# STM32_V3.net
KiCad netlist of a schematic drawn in Altium Designer
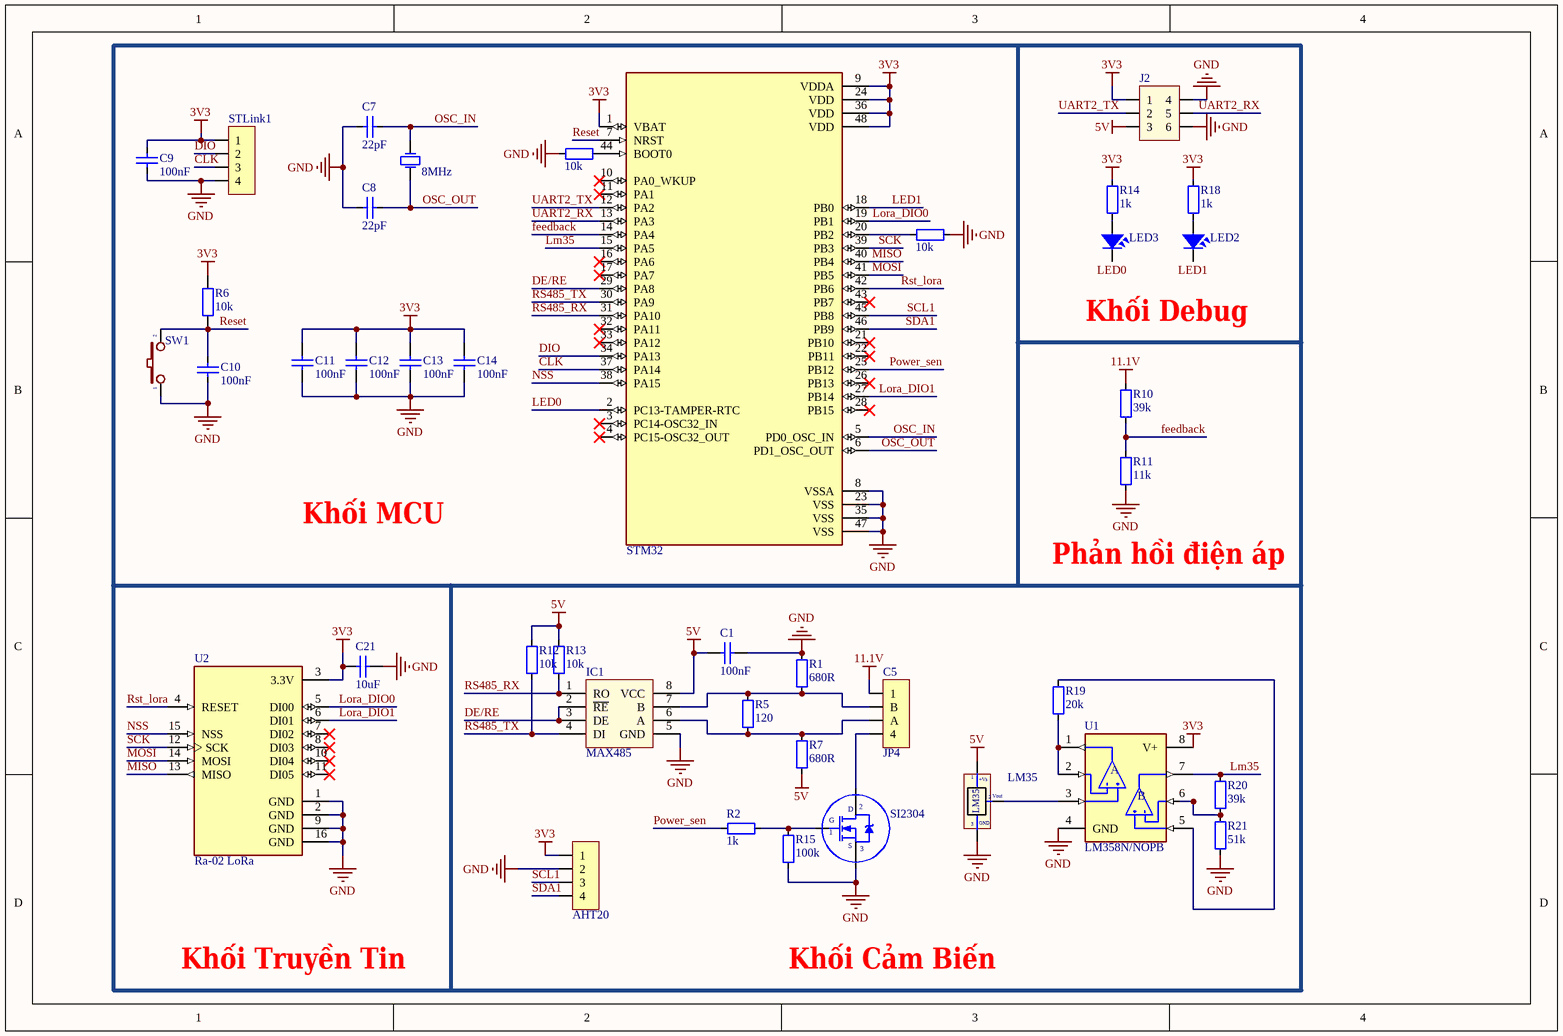
[diagram p0: STM32_V3.SchDoc]

(export (version "E")
  (design (tool "Eeschema 10.0.6"))
  (components
    (comp (ref "C1")
      (value "100nF")
      (footprint "CAP_0805")
      (description "Capacitor")
      (fields (field (name "PUBLISHER") "Altium Limited"))
      (libsource (lib "My Library") (part "CapSMD"))
    )
    (comp (ref "C5")
      (value "JP4")
      (footprint "KF4-5.08")
      (description "WR-PHD 2.54 mm Angled Socket Header")
      (fields
        (field (name "MANUFACTURER") "Würth Elektronik eiSos GmbH")
        (field (name "PARTNO") "613004143121")
        (field (name "CREATED BY") "Karrer Zheng")
      )
      (libsource (lib "") (part "JP4_1"))
    )
    (comp (ref "C7")
      (value "22pF")
      (footprint "CAP_0805")
      (description "Capacitor")
      (fields (field (name "PUBLISHER") "Altium Limited"))
      (libsource (lib "") (part "CapSMD_1"))
    )
    (comp (ref "C8")
      (value "22pF")
      (footprint "CAP_0805")
      (description "Capacitor")
      (fields (field (name "PUBLISHER") "Altium Limited"))
      (libsource (lib "") (part "CapSMD_1"))
    )
    (comp (ref "C9")
      (value "100nF")
      (footprint "CAP_0805")
      (description "Capacitor")
      (fields (field (name "PUBLISHER") "Altium Limited"))
      (libsource (lib "") (part "CapSMD_1"))
    )
    (comp (ref "C10")
      (value "100nF")
      (footprint "CAP_0805")
      (description "Capacitor")
      (fields (field (name "PUBLISHER") "Altium Limited"))
      (libsource (lib "") (part "CapSMD_1"))
    )
    (comp (ref "C11")
      (value "100nF")
      (footprint "CAP_0805")
      (description "Capacitor")
      (fields (field (name "PUBLISHER") "Altium Limited"))
      (libsource (lib "My Library") (part "CapSMD"))
    )
    (comp (ref "C12")
      (value "100nF")
      (footprint "CAP_0805")
      (description "Capacitor")
      (fields (field (name "PUBLISHER") "Altium Limited"))
      (libsource (lib "My Library") (part "CapSMD"))
    )
    (comp (ref "C13")
      (value "100nF")
      (footprint "CAP_0805")
      (description "Capacitor")
      (fields (field (name "PUBLISHER") "Altium Limited"))
      (libsource (lib "My Library") (part "CapSMD"))
    )
    (comp (ref "C14")
      (value "100nF")
      (footprint "CAP_0805")
      (description "Capacitor")
      (fields (field (name "PUBLISHER") "Altium Limited"))
      (libsource (lib "My Library") (part "CapSMD"))
    )
    (comp (ref "C19")
      (value "AHT20")
      (footprint "JP4-C1T")
      (description "WR-PHD 2.54 mm Angled Socket Header")
      (fields
        (field (name "MANUFACTURER") "Würth Elektronik eiSos GmbH")
        (field (name "PARTNO") "613004143121")
        (field (name "CREATED BY") "Karrer Zheng")
      )
      (libsource (lib "My Library") (part "JP4"))
    )
    (comp (ref "C21")
      (value "10uF")
      (footprint "CAP_0805")
      (description "Capacitor")
      (fields (field (name "PUBLISHER") "Altium Limited"))
      (libsource (lib "My Library") (part "CapSMD"))
    )
    (comp (ref "IC1")
      (value "MAX485")
      (footprint "SO-8")
      (description "RS232 - RS485 (Same sn75176)")
      (libsource (lib "My Library") (part "MAX485"))
    )
    (comp (ref "J2") (value "Connector 3x2") (footprint "JP3x2") (libsource (lib "hphonglib") (part "JP3x2")))
    (comp (ref "LED2")
      (value "LED")
      (footprint "LED-0805-Blue")
      (description "LED Single colour Green and Red")
      (libsource (lib "My Library") (part "LED"))
    )
    (comp (ref "LED3")
      (value "LED")
      (footprint "LED-0805-Blue")
      (description "LED Single colour Green and Red")
      (libsource (lib "My Library") (part "LED"))
    )
    (comp (ref "M1")
      (value "SI2304")
      (footprint "SOT23A")
      (description "Generic N Channel MOSFET")
      (libsource (lib "My Library") (part "MOSFET_N"))
    )
    (comp (ref "R1")
      (value "680R")
      (footprint "RES-SMD-0805")
      (description "Resistor")
      (fields
        (field (name "MANUFACTURER") "Generic Components")
        (field (name "PUBLISHER") "Altium Hobart Technology Centre")
      )
      (libsource (lib "My Library") (part "Resistor - SMD"))
    )
    (comp (ref "R2")
      (value "1k")
      (footprint "RES-SMD-0805")
      (description "Resistor")
      (fields
        (field (name "MANUFACTURER") "Generic Components")
        (field (name "PUBLISHER") "Altium Hobart Technology Centre")
      )
      (libsource (lib "My Library") (part "Resistor - SMD"))
    )
    (comp (ref "R3")
      (value "10k")
      (footprint "RES-SMD-0805")
      (description "Resistor")
      (fields
        (field (name "MANUFACTURER") "Generic Components")
        (field (name "PUBLISHER") "Altium Hobart Technology Centre")
      )
      (libsource (lib "My Library") (part "Resistor - SMD"))
    )
    (comp (ref "R5")
      (value "120")
      (footprint "RES-SMD-0805")
      (description "Resistor")
      (fields
        (field (name "MANUFACTURER") "Generic Components")
        (field (name "PUBLISHER") "Altium Hobart Technology Centre")
      )
      (libsource (lib "My Library") (part "Resistor - SMD"))
    )
    (comp (ref "R6")
      (value "10k")
      (footprint "RES_SMD_0805")
      (description "Resistor SMD")
      (fields
        (field (name "MANUFACTURER") "Generic Components")
        (field (name "PUBLISHER") "Altium Hobart Technology Centre")
      )
      (libsource (lib "") (part "Resistor - SMD_1"))
    )
    (comp (ref "R7")
      (value "680R")
      (footprint "RES-SMD-0805")
      (description "Resistor")
      (fields
        (field (name "MANUFACTURER") "Generic Components")
        (field (name "PUBLISHER") "Altium Hobart Technology Centre")
      )
      (libsource (lib "My Library") (part "Resistor - SMD"))
    )
    (comp (ref "R10")
      (value "39k")
      (footprint "RES-SMD-0805")
      (description "Resistor")
      (fields
        (field (name "MANUFACTURER") "Generic Components")
        (field (name "PUBLISHER") "Altium Hobart Technology Centre")
      )
      (libsource (lib "My Library") (part "Resistor - SMD"))
    )
    (comp (ref "R11")
      (value "11k")
      (footprint "RES-SMD-0805")
      (description "Resistor")
      (fields
        (field (name "MANUFACTURER") "Generic Components")
        (field (name "PUBLISHER") "Altium Hobart Technology Centre")
      )
      (libsource (lib "My Library") (part "Resistor - SMD"))
    )
    (comp (ref "R12")
      (value "10k")
      (footprint "RES-SMD-0805")
      (description "Resistor")
      (fields
        (field (name "MANUFACTURER") "Generic Components")
        (field (name "PUBLISHER") "Altium Hobart Technology Centre")
      )
      (libsource (lib "My Library") (part "Resistor - SMD"))
    )
    (comp (ref "R13")
      (value "10k")
      (footprint "RES-SMD-0805")
      (description "Resistor")
      (fields
        (field (name "MANUFACTURER") "Generic Components")
        (field (name "PUBLISHER") "Altium Hobart Technology Centre")
      )
      (libsource (lib "My Library") (part "Resistor - SMD"))
    )
    (comp (ref "R14")
      (value "1k")
      (footprint "RES-SMD-0805")
      (description "Resistor")
      (fields
        (field (name "MANUFACTURER") "Generic Components")
        (field (name "PUBLISHER") "Altium Hobart Technology Centre")
      )
      (libsource (lib "My Library") (part "Resistor - SMD"))
    )
    (comp (ref "R15")
      (value "100k")
      (footprint "RES-SMD-0805")
      (description "Resistor")
      (fields
        (field (name "MANUFACTURER") "Generic Components")
        (field (name "PUBLISHER") "Altium Hobart Technology Centre")
      )
      (libsource (lib "My Library") (part "Resistor - SMD"))
    )
    (comp (ref "R17")
      (value "10k")
      (footprint "RES-SMD-0805")
      (description "Resistor")
      (fields
        (field (name "MANUFACTURER") "Generic Components")
        (field (name "PUBLISHER") "Altium Hobart Technology Centre")
      )
      (libsource (lib "My Library") (part "Resistor - SMD"))
    )
    (comp (ref "R18")
      (value "1k")
      (footprint "RES-SMD-0805")
      (description "Resistor")
      (fields
        (field (name "MANUFACTURER") "Generic Components")
        (field (name "PUBLISHER") "Altium Hobart Technology Centre")
      )
      (libsource (lib "My Library") (part "Resistor - SMD"))
    )
    (comp (ref "R19")
      (value "20k")
      (footprint "RES-SMD-0805")
      (description "Resistor")
      (fields
        (field (name "MANUFACTURER") "Generic Components")
        (field (name "PUBLISHER") "Altium Hobart Technology Centre")
      )
      (libsource (lib "My Library") (part "Resistor - SMD"))
    )
    (comp (ref "R20")
      (value "39k")
      (footprint "RES-SMD-0805")
      (description "Resistor")
      (fields
        (field (name "MANUFACTURER") "Generic Components")
        (field (name "PUBLISHER") "Altium Hobart Technology Centre")
      )
      (libsource (lib "My Library") (part "Resistor - SMD"))
    )
    (comp (ref "R21")
      (value "51k")
      (footprint "RES-SMD-0805")
      (description "Resistor")
      (fields
        (field (name "MANUFACTURER") "Generic Components")
        (field (name "PUBLISHER") "Altium Hobart Technology Centre")
      )
      (libsource (lib "My Library") (part "Resistor - SMD"))
    )
    (comp (ref "STLink1")
      (value "JP4")
      (footprint "JP4-C1T")
      (description "WR-PHD 2.54 mm Angled Socket Header")
      (fields
        (field (name "MANUFACTURER") "Würth Elektronik eiSos GmbH")
        (field (name "PARTNO") "613004143121")
        (field (name "CREATED BY") "Karrer Zheng")
      )
      (libsource (lib "My Library") (part "JP4"))
    )
    (comp (ref "STM32")
      (value "STM32")
      (footprint "LQFP 48")
      (description "STM32 ARM-based 32-bit MCU with 64 Kbytes Flash, 64-pin LQFP, Industrial Temperature")
      (libsource (lib "My Library") (part "STM32F103C8T6"))
    )
    (comp (ref "SW1")
      (value "SW")
      (footprint "SW-SMD")
      (description "Switch button 2 pin")
      (libsource (lib "My Library") (part "SW2"))
    )
    (comp (ref "U1")
      (value "LM358N/NOPB")
      (footprint "SOIC8")
      (description "General Purpose Amplifier 2 Circuit - 8-PDIP")
      (fields (field (name "MF") "ON Semiconductor") (field (name "MP") "LM358N"))
      (libsource (lib "LM358N_NOPB") (part "LM358N/NOPB"))
    )
    (comp (ref "U2")
      (value "Ra-02 LoRa")
      (footprint "Ra-02")
      (description "LoRa Module Ra-02")
      (libsource (lib "My Library") (part "Ra-02 LoRa"))
    )
    (comp (ref "U3")
      (value "LM35")
      (footprint "QTO-92")
      (description "Teminal")
      (libsource (lib "My Library") (part "LM35"))
    )
    (comp (ref "Y1")
      (value "8MHz")
      (footprint "XTAL")
      (description "Crystal Oscillator")
      (fields (field (name "PUBLISHER") "Altium Limited"))
      (libsource (lib "My Library") (part "XTAL"))
    )
  )
  (nets
    (net (code "1") (name "/CLK") (class "Default")
      (node (ref "STLink1") (pin "3") (pinfunction "3_3") (pintype "passive"))
      (node (ref "STM32") (pin "37") (pinfunction "PA14_37") (pintype "bidirectional"))
    )
    (net (code "2") (name "/DE{slash}RE") (class "Default")
      (node (ref "IC1") (pin "2") (pinfunction "~{RE}_2") (pintype "passive"))
      (node (ref "IC1") (pin "3") (pinfunction "DE_3") (pintype "passive"))
      (node (ref "STM32") (pin "29") (pinfunction "PA8_29") (pintype "bidirectional"))
    )
    (net (code "3") (name "/DIO") (class "Default")
      (node (ref "STLink1") (pin "2") (pinfunction "2_2") (pintype "passive"))
      (node (ref "STM32") (pin "34") (pinfunction "PA13_34") (pintype "bidirectional"))
    )
    (net (code "4") (name "/LED0") (class "Default")
      (node (ref "LED3") (pin "2") (pinfunction "2_2") (pintype "passive"))
      (node (ref "STM32") (pin "2") (pinfunction "PC13-TAMPER-RTC_2") (pintype "bidirectional"))
    )
    (net (code "5") (name "/LED1") (class "Default")
      (node (ref "LED2") (pin "2") (pinfunction "2_2") (pintype "passive"))
      (node (ref "STM32") (pin "18") (pinfunction "PB0_18") (pintype "bidirectional"))
    )
    (net (code "6") (name "/Lm35") (class "Default")
      (node (ref "R20") (pin "1") (pinfunction "1_1") (pintype "passive"))
      (node (ref "STM32") (pin "15") (pinfunction "PA5_15") (pintype "bidirectional"))
      (node (ref "U1") (pin "7") (pinfunction "OUTB_7") (pintype "output"))
    )
    (net (code "7") (name "/Lora_DIO0") (class "Default")
      (node (ref "STM32") (pin "19") (pinfunction "PB1_19") (pintype "bidirectional"))
      (node (ref "U2") (pin "5") (pinfunction "DI00_5") (pintype "bidirectional"))
    )
    (net (code "8") (name "/Lora_DIO1") (class "Default")
      (node (ref "STM32") (pin "27") (pinfunction "PB14_27") (pintype "bidirectional"))
      (node (ref "U2") (pin "6") (pinfunction "DI01_6") (pintype "bidirectional"))
    )
    (net (code "9") (name "/MISO") (class "Default")
      (node (ref "STM32") (pin "40") (pinfunction "PB4_40") (pintype "bidirectional"))
      (node (ref "U2") (pin "13") (pinfunction "MISO_13") (pintype "output"))
    )
    (net (code "10") (name "/MOSI") (class "Default")
      (node (ref "STM32") (pin "41") (pinfunction "PB5_41") (pintype "bidirectional"))
      (node (ref "U2") (pin "14") (pinfunction "MOSI_14") (pintype "input"))
    )
    (net (code "11") (name "/NSS") (class "Default")
      (node (ref "STM32") (pin "38") (pinfunction "PA15_38") (pintype "bidirectional"))
      (node (ref "U2") (pin "15") (pinfunction "NSS_15") (pintype "input"))
    )
    (net (code "12") (name "/OSC_IN") (class "Default")
      (node (ref "C7") (pin "1") (pinfunction "1_1") (pintype "passive"))
      (node (ref "STM32") (pin "5") (pinfunction "PD0_OSC_IN_5") (pintype "bidirectional"))
      (node (ref "Y1") (pin "2") (pinfunction "OSC2_2") (pintype "passive"))
    )
    (net (code "13") (name "/OSC_OUT") (class "Default")
      (node (ref "C8") (pin "1") (pinfunction "1_1") (pintype "passive"))
      (node (ref "STM32") (pin "6") (pinfunction "PD1_OSC_OUT_6") (pintype "bidirectional"))
      (node (ref "Y1") (pin "1") (pinfunction "OSC1_1") (pintype "passive"))
    )
    (net (code "14") (name "/Power_sen") (class "Default")
      (node (ref "R2") (pin "1") (pinfunction "1_1") (pintype "passive"))
      (node (ref "STM32") (pin "25") (pinfunction "PB12_25") (pintype "bidirectional"))
    )
    (net (code "15") (name "/RS485_RX") (class "Default")
      (node (ref "IC1") (pin "1") (pinfunction "RO_1") (pintype "passive"))
      (node (ref "R13") (pin "2") (pinfunction "2_2") (pintype "passive"))
      (node (ref "STM32") (pin "31") (pinfunction "PA10_31") (pintype "bidirectional"))
    )
    (net (code "16") (name "/RS485_TX") (class "Default")
      (node (ref "IC1") (pin "4") (pinfunction "DI_4") (pintype "passive"))
      (node (ref "R12") (pin "2") (pinfunction "2_2") (pintype "passive"))
      (node (ref "STM32") (pin "30") (pinfunction "PA9_30") (pintype "bidirectional"))
    )
    (net (code "17") (name "/Reset") (class "Default")
      (node (ref "C10") (pin "1") (pinfunction "1_1") (pintype "passive"))
      (node (ref "R6") (pin "2") (pinfunction "2_2") (pintype "passive"))
      (node (ref "STM32") (pin "7") (pinfunction "NRST_7") (pintype "input"))
      (node (ref "SW1") (pin "2") (pinfunction "2_2") (pintype "passive"))
    )
    (net (code "18") (name "/Rst_lora") (class "Default")
      (node (ref "STM32") (pin "42") (pinfunction "PB6_42") (pintype "bidirectional"))
      (node (ref "U2") (pin "4") (pinfunction "RESET_4") (pintype "input"))
    )
    (net (code "19") (name "/SCK") (class "Default")
      (node (ref "STM32") (pin "39") (pinfunction "PB3_39") (pintype "bidirectional"))
      (node (ref "U2") (pin "12") (pinfunction "SCK_12") (pintype "input"))
    )
    (net (code "20") (name "/SCL1") (class "Default")
      (node (ref "C19") (pin "3") (pinfunction "3_3") (pintype "passive"))
      (node (ref "STM32") (pin "45") (pinfunction "PB8_45") (pintype "bidirectional"))
    )
    (net (code "21") (name "/SDA1") (class "Default")
      (node (ref "C19") (pin "4") (pinfunction "4_4") (pintype "passive"))
      (node (ref "STM32") (pin "46") (pinfunction "PB9_46") (pintype "bidirectional"))
    )
    (net (code "22") (name "/UART2_RX") (class "Default")
      (node (ref "J2") (pin "5") (pinfunction "5_5") (pintype "passive"))
      (node (ref "STM32") (pin "13") (pinfunction "PA3_13") (pintype "bidirectional"))
    )
    (net (code "23") (name "/UART2_TX") (class "Default")
      (node (ref "J2") (pin "2") (pinfunction "2_2") (pintype "passive"))
      (node (ref "STM32") (pin "12") (pinfunction "PA2_12") (pintype "bidirectional"))
    )
    (net (code "24") (name "/feedback") (class "Default")
      (node (ref "R10") (pin "2") (pinfunction "2_2") (pintype "passive"))
      (node (ref "R11") (pin "1") (pinfunction "1_1") (pintype "passive"))
      (node (ref "STM32") (pin "14") (pinfunction "PA4_14") (pintype "bidirectional"))
    )
    (net (code "25") (name "3V3") (class "Default")
      (node (ref "C11") (pin "1") (pinfunction "1_1") (pintype "passive"))
      (node (ref "C12") (pin "1") (pinfunction "1_1") (pintype "passive"))
      (node (ref "C13") (pin "1") (pinfunction "1_1") (pintype "passive"))
      (node (ref "C14") (pin "1") (pinfunction "1_1") (pintype "passive"))
      (node (ref "C19") (pin "1") (pinfunction "1_1") (pintype "passive"))
      (node (ref "C21") (pin "1") (pinfunction "1_1") (pintype "passive"))
      (node (ref "C9") (pin "1") (pinfunction "1_1") (pintype "passive"))
      (node (ref "J2") (pin "1") (pinfunction "1_1") (pintype "passive"))
      (node (ref "R14") (pin "1") (pinfunction "1_1") (pintype "passive"))
      (node (ref "R18") (pin "1") (pinfunction "1_1") (pintype "passive"))
      (node (ref "R6") (pin "1") (pinfunction "1_1") (pintype "passive"))
      (node (ref "STLink1") (pin "1") (pinfunction "1_1") (pintype "passive"))
      (node (ref "STM32") (pin "1") (pinfunction "VBAT_1") (pintype "bidirectional"))
      (node (ref "STM32") (pin "24") (pinfunction "VDD_24") (pintype "power_in"))
      (node (ref "STM32") (pin "36") (pinfunction "VDD_36") (pintype "power_in"))
      (node (ref "STM32") (pin "48") (pinfunction "VDD_48") (pintype "power_in"))
      (node (ref "STM32") (pin "9") (pinfunction "VDDA_9") (pintype "power_in"))
      (node (ref "U1") (pin "8") (pinfunction "V+_8") (pintype "power_in"))
      (node (ref "U2") (pin "3") (pinfunction "3.3V_3") (pintype "power_in"))
    )
    (net (code "26") (name "5V") (class "Default")
      (node (ref "C1") (pin "1") (pinfunction "1_1") (pintype "passive"))
      (node (ref "IC1") (pin "8") (pinfunction "VCC_8") (pintype "passive"))
      (node (ref "J2") (pin "3") (pinfunction "3_3") (pintype "passive"))
      (node (ref "R12") (pin "1") (pinfunction "1_1") (pintype "passive"))
      (node (ref "R13") (pin "1") (pinfunction "1_1") (pintype "passive"))
      (node (ref "R7") (pin "2") (pinfunction "2_2") (pintype "passive"))
      (node (ref "U3") (pin "1") (pinfunction "+Vs_1") (pintype "passive"))
    )
    (net (code "27") (name "11.1V") (class "Default")
      (node (ref "C5") (pin "1") (pinfunction "1_1") (pintype "passive"))
      (node (ref "R10") (pin "1") (pinfunction "1_1") (pintype "passive"))
    )
    (net (code "28") (name "GND") (class "Default")
      (node (ref "C1") (pin "2") (pinfunction "2_2") (pintype "passive"))
      (node (ref "C10") (pin "2") (pinfunction "2_2") (pintype "passive"))
      (node (ref "C11") (pin "2") (pinfunction "2_2") (pintype "passive"))
      (node (ref "C12") (pin "2") (pinfunction "2_2") (pintype "passive"))
      (node (ref "C13") (pin "2") (pinfunction "2_2") (pintype "passive"))
      (node (ref "C14") (pin "2") (pinfunction "2_2") (pintype "passive"))
      (node (ref "C19") (pin "2") (pinfunction "2_2") (pintype "passive"))
      (node (ref "C21") (pin "2") (pinfunction "2_2") (pintype "passive"))
      (node (ref "C7") (pin "2") (pinfunction "2_2") (pintype "passive"))
      (node (ref "C8") (pin "2") (pinfunction "2_2") (pintype "passive"))
      (node (ref "C9") (pin "2") (pinfunction "2_2") (pintype "passive"))
      (node (ref "IC1") (pin "5") (pinfunction "GND_5") (pintype "passive"))
      (node (ref "J2") (pin "4") (pinfunction "4_4") (pintype "passive"))
      (node (ref "J2") (pin "6") (pinfunction "6_6") (pintype "passive"))
      (node (ref "M1") (pin "3") (pinfunction "S_3") (pintype "passive"))
      (node (ref "R1") (pin "1") (pinfunction "1_1") (pintype "passive"))
      (node (ref "R11") (pin "2") (pinfunction "2_2") (pintype "passive"))
      (node (ref "R15") (pin "1") (pinfunction "1_1") (pintype "passive"))
      (node (ref "R17") (pin "2") (pinfunction "2_2") (pintype "passive"))
      (node (ref "R21") (pin "2") (pinfunction "2_2") (pintype "passive"))
      (node (ref "R3") (pin "1") (pinfunction "1_1") (pintype "passive"))
      (node (ref "STLink1") (pin "4") (pinfunction "4_4") (pintype "passive"))
      (node (ref "STM32") (pin "23") (pinfunction "VSS_23") (pintype "power_in"))
      (node (ref "STM32") (pin "35") (pinfunction "VSS_35") (pintype "power_in"))
      (node (ref "STM32") (pin "47") (pinfunction "VSS_47") (pintype "power_in"))
      (node (ref "STM32") (pin "8") (pinfunction "VSSA_8") (pintype "power_in"))
      (node (ref "SW1") (pin "1") (pinfunction "1_1") (pintype "passive"))
      (node (ref "U1") (pin "4") (pinfunction "GND_4") (pintype "power_in"))
      (node (ref "U2") (pin "1") (pinfunction "GND_1") (pintype "power_in"))
      (node (ref "U2") (pin "16") (pinfunction "GND_16") (pintype "power_in"))
      (node (ref "U2") (pin "2") (pinfunction "GND_2") (pintype "power_in"))
      (node (ref "U2") (pin "9") (pinfunction "GND_9") (pintype "power_in"))
      (node (ref "U3") (pin "3") (pinfunction "-_3") (pintype "passive"))
    )
    (net (code "29") (name "Net-(C5-A)") (class "Default")
      (node (ref "C5") (pin "3") (pinfunction "A_3") (pintype "passive"))
      (node (ref "IC1") (pin "6") (pinfunction "A_6") (pintype "passive"))
      (node (ref "R5") (pin "2") (pinfunction "2_2") (pintype "passive"))
      (node (ref "R7") (pin "1") (pinfunction "1_1") (pintype "passive"))
    )
    (net (code "30") (name "Net-(C5-B)") (class "Default")
      (node (ref "C5") (pin "2") (pinfunction "B_2") (pintype "passive"))
      (node (ref "IC1") (pin "7") (pinfunction "B_7") (pintype "passive"))
      (node (ref "R1") (pin "2") (pinfunction "2_2") (pintype "passive"))
      (node (ref "R5") (pin "1") (pinfunction "1_1") (pintype "passive"))
    )
    (net (code "31") (name "Net-(LED2-Pad1)") (class "Default")
      (node (ref "LED2") (pin "1") (pinfunction "1_1") (pintype "passive"))
      (node (ref "R18") (pin "2") (pinfunction "2_2") (pintype "passive"))
    )
    (net (code "32") (name "Net-(LED3-Pad1)") (class "Default")
      (node (ref "LED3") (pin "1") (pinfunction "1_1") (pintype "passive"))
      (node (ref "R14") (pin "2") (pinfunction "2_2") (pintype "passive"))
    )
    (net (code "33") (name "Net-(M1-D)") (class "Default")
      (node (ref "C5") (pin "4") (pinfunction "4_4") (pintype "passive"))
      (node (ref "M1") (pin "2") (pinfunction "D_2") (pintype "passive"))
    )
    (net (code "34") (name "Net-(M1-G)") (class "Default")
      (node (ref "M1") (pin "1") (pinfunction "G_1") (pintype "passive"))
      (node (ref "R15") (pin "2") (pinfunction "2_2") (pintype "passive"))
      (node (ref "R2") (pin "2") (pinfunction "2_2") (pintype "passive"))
    )
    (net (code "35") (name "Net-(STM32-BOOT0)") (class "Default")
      (node (ref "R17") (pin "1") (pinfunction "1_1") (pintype "passive"))
      (node (ref "STM32") (pin "44") (pinfunction "BOOT0_44") (pintype "input"))
    )
    (net (code "36") (name "Net-(STM32-PB2)") (class "Default")
      (node (ref "R3") (pin "2") (pinfunction "2_2") (pintype "passive"))
      (node (ref "STM32") (pin "20") (pinfunction "PB2_20") (pintype "bidirectional"))
    )
    (net (code "37") (name "Net-(U1-+INA)") (class "Default")
      (node (ref "U1") (pin "3") (pinfunction "+INA_3") (pintype "input"))
      (node (ref "U3") (pin "2") (pinfunction "Vout_2") (pintype "passive"))
    )
    (net (code "38") (name "Net-(U1-+INB)") (class "Default")
      (node (ref "R19") (pin "1") (pinfunction "1_1") (pintype "passive"))
      (node (ref "U1") (pin "5") (pinfunction "+INB_5") (pintype "input"))
    )
    (net (code "39") (name "Net-(U1--INA)") (class "Default")
      (node (ref "R19") (pin "2") (pinfunction "2_2") (pintype "passive"))
      (node (ref "U1") (pin "1") (pinfunction "OUTA_1") (pintype "output"))
      (node (ref "U1") (pin "2") (pinfunction "-INA_2") (pintype "input"))
    )
    (net (code "40") (name "Net-(U1--INB)") (class "Default")
      (node (ref "R20") (pin "2") (pinfunction "2_2") (pintype "passive"))
      (node (ref "R21") (pin "1") (pinfunction "1_1") (pintype "passive"))
      (node (ref "U1") (pin "6") (pinfunction "-INB_6") (pintype "input"))
    )
    (net (code "41") (name "unconnected-(STM32-PA0_WKUP-Pad10)") (class "Default")
      (node (ref "STM32") (pin "10") (pinfunction "PA0_WKUP_10") (pintype "bidirectional+no_connect"))
    )
    (net (code "42") (name "unconnected-(STM32-PA1-Pad11)") (class "Default")
      (node (ref "STM32") (pin "11") (pinfunction "PA1_11") (pintype "bidirectional+no_connect"))
    )
    (net (code "43") (name "unconnected-(STM32-PA6-Pad16)") (class "Default")
      (node (ref "STM32") (pin "16") (pinfunction "PA6_16") (pintype "bidirectional+no_connect"))
    )
    (net (code "44") (name "unconnected-(STM32-PA7-Pad17)") (class "Default")
      (node (ref "STM32") (pin "17") (pinfunction "PA7_17") (pintype "bidirectional+no_connect"))
    )
    (net (code "45") (name "unconnected-(STM32-PA11-Pad32)") (class "Default")
      (node (ref "STM32") (pin "32") (pinfunction "PA11_32") (pintype "bidirectional+no_connect"))
    )
    (net (code "46") (name "unconnected-(STM32-PA12-Pad33)") (class "Default")
      (node (ref "STM32") (pin "33") (pinfunction "PA12_33") (pintype "bidirectional+no_connect"))
    )
    (net (code "47") (name "unconnected-(STM32-PB7-Pad43)") (class "Default")
      (node (ref "STM32") (pin "43") (pinfunction "PB7_43") (pintype "bidirectional+no_connect"))
    )
    (net (code "48") (name "unconnected-(STM32-PB10-Pad21)") (class "Default")
      (node (ref "STM32") (pin "21") (pinfunction "PB10_21") (pintype "bidirectional+no_connect"))
    )
    (net (code "49") (name "unconnected-(STM32-PB11-Pad22)") (class "Default")
      (node (ref "STM32") (pin "22") (pinfunction "PB11_22") (pintype "bidirectional+no_connect"))
    )
    (net (code "50") (name "unconnected-(STM32-PB13-Pad26)") (class "Default")
      (node (ref "STM32") (pin "26") (pinfunction "PB13_26") (pintype "bidirectional+no_connect"))
    )
    (net (code "51") (name "unconnected-(STM32-PB15-Pad28)") (class "Default")
      (node (ref "STM32") (pin "28") (pinfunction "PB15_28") (pintype "bidirectional+no_connect"))
    )
    (net (code "52") (name "unconnected-(STM32-PC14-OSC32_IN-Pad3)") (class "Default")
      (node (ref "STM32") (pin "3") (pinfunction "PC14-OSC32_IN_3") (pintype "bidirectional+no_connect"))
    )
    (net (code "53") (name "unconnected-(STM32-PC15-OSC32_OUT-Pad4)") (class "Default")
      (node (ref "STM32") (pin "4") (pinfunction "PC15-OSC32_OUT_4") (pintype "bidirectional+no_connect"))
    )
    (net (code "54") (name "unconnected-(U2-DI02-Pad7)") (class "Default")
      (node (ref "U2") (pin "7") (pinfunction "DI02_7") (pintype "bidirectional+no_connect"))
    )
    (net (code "55") (name "unconnected-(U2-DI03-Pad8)") (class "Default")
      (node (ref "U2") (pin "8") (pinfunction "DI03_8") (pintype "bidirectional+no_connect"))
    )
    (net (code "56") (name "unconnected-(U2-DI04-Pad10)") (class "Default")
      (node (ref "U2") (pin "10") (pinfunction "DI04_10") (pintype "bidirectional+no_connect"))
    )
    (net (code "57") (name "unconnected-(U2-DI05-Pad11)") (class "Default")
      (node (ref "U2") (pin "11") (pinfunction "DI05_11") (pintype "bidirectional+no_connect"))
    )
  )
)
